# SCH_CJ4-lights-panel.net
KiCad netlist of a schematic drawn in EasyEDA
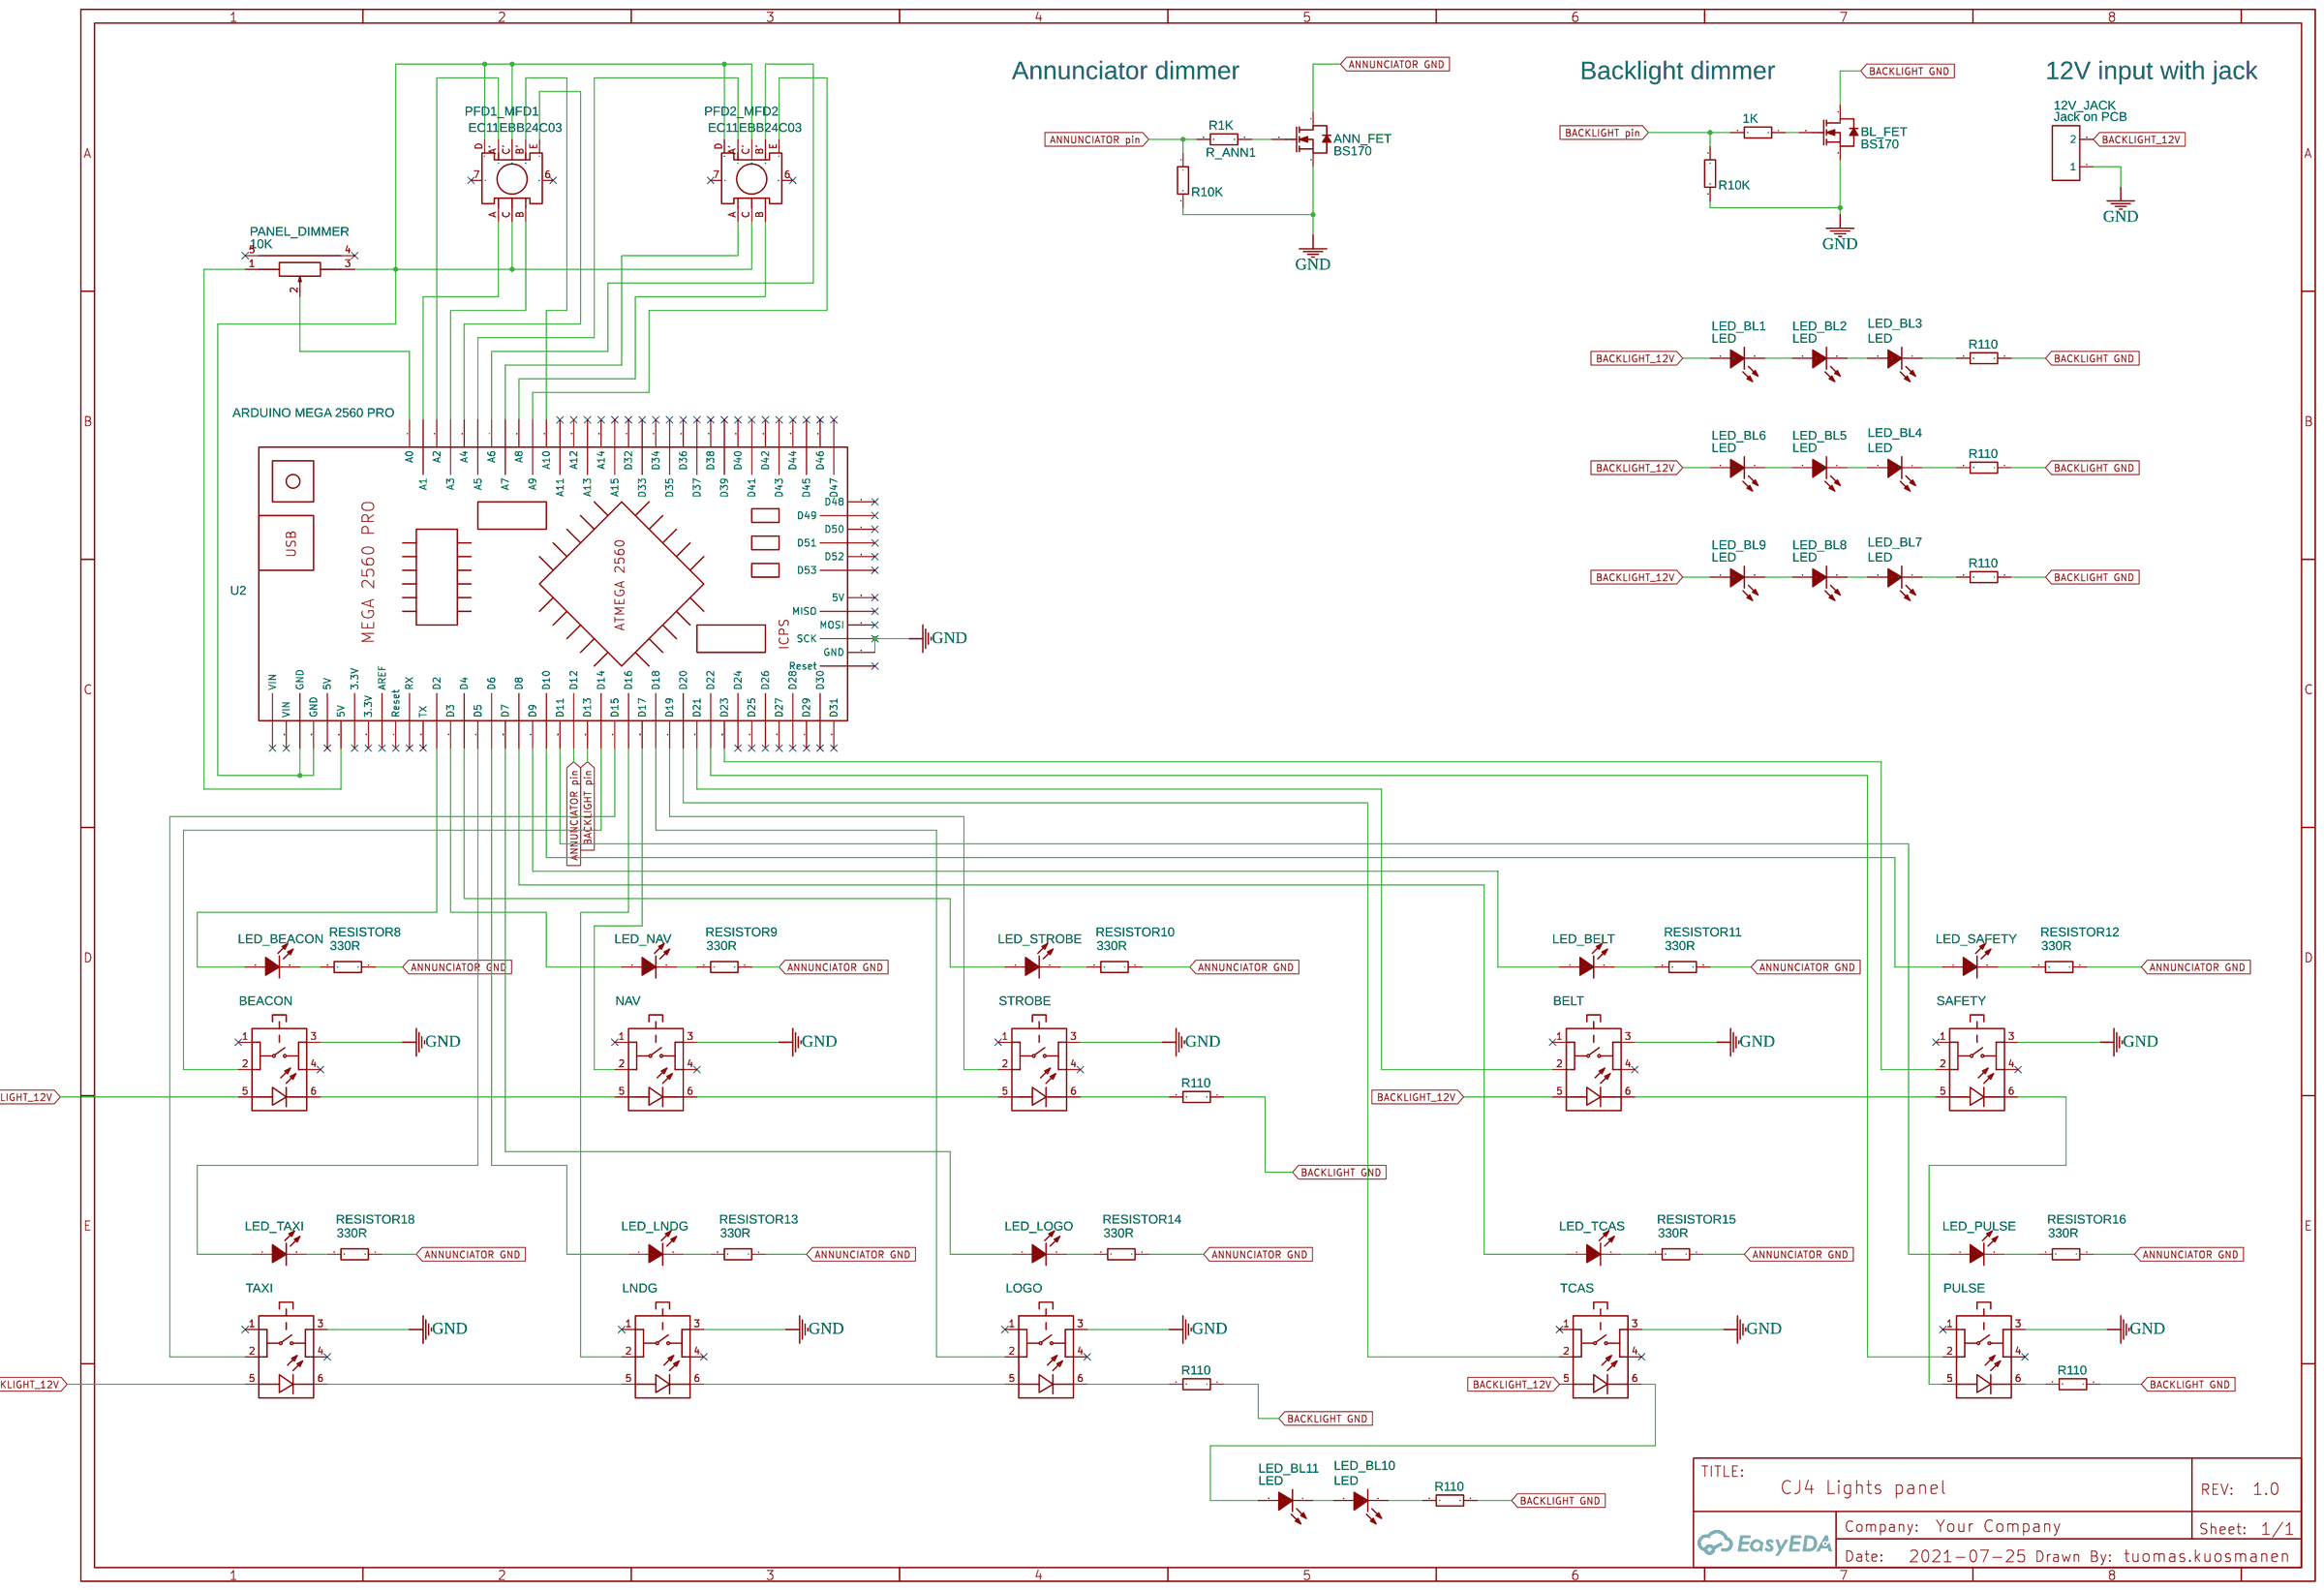
[diagram p0: schematic sheet]

(export (version "E")
  (design (tool "Eeschema 10.0.6"))
  (components
    (comp (ref "1MM_LED_THROUGH_HOLE")
      (value "LED_TAXI")
      (fields
        (field (name "BOM_Manufacturer Part") "LEDOrange orange 3AO4UD")
        (field (name "BOM_Supplier Part") "C62095")
      )
      (libsource (lib "") (part "LEDOrange orange 3AO4UD_3"))
    )
    (comp (ref "2MM_LED_THROUGH_HOLE")
      (value "LED_LNDG")
      (fields
        (field (name "BOM_Manufacturer Part") "LEDOrange orange 3AO4UD")
        (field (name "BOM_Supplier Part") "C62095")
      )
      (libsource (lib "") (part "LEDOrange orange 3AO4UD_1"))
    )
    (comp (ref "3MM_LED_THROUGH_HOLE")
      (value "LED_NAV")
      (fields
        (field (name "BOM_Manufacturer Part") "LEDOrange orange 3AO4UD")
        (field (name "BOM_Supplier Part") "C62095")
      )
      (libsource (lib "") (part "LEDOrange orange 3AO4UD_5"))
    )
    (comp (ref "4MM_LED_THROUGH_HOLE")
      (value "LED_LOGO")
      (fields
        (field (name "BOM_Manufacturer Part") "LEDOrange orange 3AO4UD")
        (field (name "BOM_Supplier Part") "C62095")
      )
      (libsource (lib "") (part "LEDOrange orange 3AO4UD_6"))
    )
    (comp (ref "5MM_LED_THROUGH_HOLE")
      (value "LED_BEACON")
      (fields
        (field (name "BOM_Manufacturer Part") "LEDOrange orange 3AO4UD")
        (field (name "BOM_Supplier Part") "C62095")
      )
      (libsource (lib "") (part "LEDOrange orange 3AO4UD_9"))
    )
    (comp (ref "6MM_LED_THROUGH_HOLE")
      (value "LED_STROBE")
      (fields
        (field (name "BOM_Manufacturer Part") "LEDOrange orange 3AO4UD")
        (field (name "BOM_Supplier Part") "C62095")
      )
      (libsource (lib "") (part "LEDOrange orange 3AO4UD_2"))
    )
    (comp (ref "7MM_LED_THROUGH_HOLE")
      (value "LED_SAFETY")
      (fields
        (field (name "BOM_Manufacturer Part") "LEDOrange orange 3AO4UD")
        (field (name "BOM_Supplier Part") "C62095")
      )
      (libsource (lib "") (part "LEDOrange orange 3AO4UD_7"))
    )
    (comp (ref "8MM_LED_THROUGH_HOLE")
      (value "LED_PULSE")
      (fields
        (field (name "BOM_Manufacturer Part") "LEDOrange orange 3AO4UD")
        (field (name "BOM_Supplier Part") "C62095")
      )
      (libsource (lib "") (part "LEDOrange orange 3AO4UD"))
    )
    (comp (ref "9MM_LED_THROUGH_HOLE")
      (value "LED_BELT")
      (fields
        (field (name "BOM_Manufacturer Part") "LEDOrange orange 3AO4UD")
        (field (name "BOM_Supplier Part") "C62095")
      )
      (libsource (lib "") (part "LEDOrange orange 3AO4UD_8"))
    )
    (comp (ref "10MM_LED_THROUGH_HOLE")
      (value "LED_TCAS")
      (fields
        (field (name "BOM_Manufacturer Part") "LEDOrange orange 3AO4UD")
        (field (name "BOM_Supplier Part") "C62095")
      )
      (libsource (lib "") (part "LEDOrange orange 3AO4UD_4"))
    )
    (comp (ref "12V_JACK") (value "Jack on PCB") (libsource (lib "") (part "J-Header-Male-2.54_1x2")))
    (comp (ref "ANN_FET")
      (value "BS170")
      (fields (field (name "BOM_Supplier Part") "C111691"))
      (libsource (lib "") (part "BS170"))
    )
    (comp (ref "BL_FET")
      (value "BS170")
      (fields (field (name "BOM_Supplier Part") "C111691"))
      (libsource (lib "") (part "BS170_1"))
    )
    (comp (ref "HEADING_HOLD1")
      (value "BEACON")
      (fields (field (name "BOM_Manufacturer Part") "1052612"))
      (libsource (lib "") (part "MULTIMEC 3FTH980 - Key Switch, 50 mA, 24 VDC, MEC"))
    )
    (comp (ref "HEADING_HOLD2")
      (value "TAXI")
      (fields (field (name "BOM_Manufacturer Part") "1052612"))
      (libsource (lib "") (part "MULTIMEC 3FTH980 - Key Switch, 50 mA, 24 VDC, MEC"))
    )
    (comp (ref "HEADING_HOLD3")
      (value "LNDG")
      (fields (field (name "BOM_Manufacturer Part") "1052612"))
      (libsource (lib "") (part "MULTIMEC 3FTH980 - Key Switch, 50 mA, 24 VDC, MEC"))
    )
    (comp (ref "HEADING_HOLD4")
      (value "NAV")
      (fields (field (name "BOM_Manufacturer Part") "1052612"))
      (libsource (lib "") (part "MULTIMEC 3FTH980 - Key Switch, 50 mA, 24 VDC, MEC"))
    )
    (comp (ref "HEADING_HOLD5")
      (value "LOGO")
      (fields (field (name "BOM_Manufacturer Part") "1052612"))
      (libsource (lib "") (part "MULTIMEC 3FTH980 - Key Switch, 50 mA, 24 VDC, MEC"))
    )
    (comp (ref "HEADING_HOLD6")
      (value "STROBE")
      (fields (field (name "BOM_Manufacturer Part") "1052612"))
      (libsource (lib "") (part "MULTIMEC 3FTH980 - Key Switch, 50 mA, 24 VDC, MEC"))
    )
    (comp (ref "HEADING_HOLD7")
      (value "SAFETY")
      (fields (field (name "BOM_Manufacturer Part") "1052612"))
      (libsource (lib "") (part "MULTIMEC 3FTH980 - Key Switch, 50 mA, 24 VDC, MEC"))
    )
    (comp (ref "HEADING_HOLD8")
      (value "PULSE")
      (fields (field (name "BOM_Manufacturer Part") "1052612"))
      (libsource (lib "") (part "MULTIMEC 3FTH980 - Key Switch, 50 mA, 24 VDC, MEC"))
    )
    (comp (ref "HEADING_HOLD9")
      (value "BELT")
      (fields (field (name "BOM_Manufacturer Part") "1052612"))
      (libsource (lib "") (part "MULTIMEC 3FTH980 - Key Switch, 50 mA, 24 VDC, MEC"))
    )
    (comp (ref "HEADING_HOLD10")
      (value "TCAS")
      (fields (field (name "BOM_Manufacturer Part") "1052612"))
      (libsource (lib "") (part "MULTIMEC 3FTH980 - Key Switch, 50 mA, 24 VDC, MEC"))
    )
    (comp (ref "LED_BL1")
      (value "LED")
      (fields
        (field (name "BOM_Manufacturer Part") "HQ17-2102UYOC")
        (field (name "BOM_Supplier Part") "C154481")
      )
      (libsource (lib "") (part "HQ17-2102UYOC"))
    )
    (comp (ref "LED_BL2")
      (value "LED")
      (fields
        (field (name "BOM_Manufacturer Part") "HQ17-2102UYOC")
        (field (name "BOM_Supplier Part") "C154481")
      )
      (libsource (lib "") (part "HQ17-2102UYOC"))
    )
    (comp (ref "LED_BL3")
      (value "LED")
      (fields
        (field (name "BOM_Manufacturer Part") "HQ17-2102UYOC")
        (field (name "BOM_Supplier Part") "C154481")
      )
      (libsource (lib "") (part "HQ17-2102UYOC"))
    )
    (comp (ref "LED_BL4")
      (value "LED")
      (fields
        (field (name "BOM_Manufacturer Part") "HQ17-2102UYOC")
        (field (name "BOM_Supplier Part") "C154481")
      )
      (libsource (lib "") (part "HQ17-2102UYOC"))
    )
    (comp (ref "LED_BL5")
      (value "LED")
      (fields
        (field (name "BOM_Manufacturer Part") "HQ17-2102UYOC")
        (field (name "BOM_Supplier Part") "C154481")
      )
      (libsource (lib "") (part "HQ17-2102UYOC"))
    )
    (comp (ref "LED_BL6")
      (value "LED")
      (fields
        (field (name "BOM_Manufacturer Part") "HQ17-2102UYOC")
        (field (name "BOM_Supplier Part") "C154481")
      )
      (libsource (lib "") (part "HQ17-2102UYOC"))
    )
    (comp (ref "LED_BL7")
      (value "LED")
      (fields
        (field (name "BOM_Manufacturer Part") "HQ17-2102UYOC")
        (field (name "BOM_Supplier Part") "C154481")
      )
      (libsource (lib "") (part "HQ17-2102UYOC"))
    )
    (comp (ref "LED_BL8")
      (value "LED")
      (fields
        (field (name "BOM_Manufacturer Part") "HQ17-2102UYOC")
        (field (name "BOM_Supplier Part") "C154481")
      )
      (libsource (lib "") (part "HQ17-2102UYOC"))
    )
    (comp (ref "LED_BL9")
      (value "LED")
      (fields
        (field (name "BOM_Manufacturer Part") "HQ17-2102UYOC")
        (field (name "BOM_Supplier Part") "C154481")
      )
      (libsource (lib "") (part "HQ17-2102UYOC"))
    )
    (comp (ref "LED_BL10")
      (value "LED")
      (fields
        (field (name "BOM_Manufacturer Part") "HQ17-2102UYOC")
        (field (name "BOM_Supplier Part") "C154481")
      )
      (libsource (lib "") (part "HQ17-2102UYOC"))
    )
    (comp (ref "LED_BL11")
      (value "LED")
      (fields
        (field (name "BOM_Manufacturer Part") "HQ17-2102UYOC")
        (field (name "BOM_Supplier Part") "C154481")
      )
      (libsource (lib "") (part "HQ17-2102UYOC"))
    )
    (comp (ref "PANEL_DIMMER")
      (value "10K")
      (fields
        (field (name "BOM_Manufacturer Part") "RK09K1130A70")
        (field (name "BOM_Supplier Part") "C351173")
      )
      (libsource (lib "") (part "RK09K1130A70"))
    )
    (comp (ref "PFD1_MFD1")
      (value "EC11EBB24C03")
      (fields (field (name "BOM_Supplier Part") "C470790"))
      (libsource (lib "") (part "EC11EBB24C03_1"))
    )
    (comp (ref "PFD2_MFD2")
      (value "EC11EBB24C03")
      (fields (field (name "BOM_Supplier Part") "C470790"))
      (libsource (lib "") (part "EC11EBB24C03"))
    )
    (comp (ref "PROTECT_BL1")
      (value "1K")
      (fields
        (field (name "BOM_Manufacturer Part") "1206W4J0331T5E")
        (field (name "BOM_Supplier Part") "C25374")
      )
      (libsource (lib "") (part "1206W4J0331T5E_3"))
    )
    (comp (ref "RESISTOR8")
      (value "330R")
      (fields
        (field (name "BOM_Manufacturer Part") "1206W4J0331T5E")
        (field (name "BOM_Supplier Part") "C25374")
      )
      (libsource (lib "") (part "1206W4J0331T5E"))
    )
    (comp (ref "RESISTOR9")
      (value "330R")
      (fields
        (field (name "BOM_Manufacturer Part") "1206W4J0331T5E")
        (field (name "BOM_Supplier Part") "C25374")
      )
      (libsource (lib "") (part "1206W4J0331T5E"))
    )
    (comp (ref "RESISTOR10")
      (value "330R")
      (fields
        (field (name "BOM_Manufacturer Part") "1206W4J0331T5E")
        (field (name "BOM_Supplier Part") "C25374")
      )
      (libsource (lib "") (part "1206W4J0331T5E"))
    )
    (comp (ref "RESISTOR11")
      (value "330R")
      (fields
        (field (name "BOM_Manufacturer Part") "1206W4J0331T5E")
        (field (name "BOM_Supplier Part") "C25374")
      )
      (libsource (lib "") (part "1206W4J0331T5E"))
    )
    (comp (ref "RESISTOR12")
      (value "330R")
      (fields
        (field (name "BOM_Manufacturer Part") "1206W4J0331T5E")
        (field (name "BOM_Supplier Part") "C25374")
      )
      (libsource (lib "") (part "1206W4J0331T5E"))
    )
    (comp (ref "RESISTOR13")
      (value "330R")
      (fields
        (field (name "BOM_Manufacturer Part") "1206W4J0331T5E")
        (field (name "BOM_Supplier Part") "C25374")
      )
      (libsource (lib "") (part "1206W4J0331T5E"))
    )
    (comp (ref "RESISTOR14")
      (value "330R")
      (fields
        (field (name "BOM_Manufacturer Part") "1206W4J0331T5E")
        (field (name "BOM_Supplier Part") "C25374")
      )
      (libsource (lib "") (part "1206W4J0331T5E"))
    )
    (comp (ref "RESISTOR15")
      (value "330R")
      (fields
        (field (name "BOM_Manufacturer Part") "1206W4J0331T5E")
        (field (name "BOM_Supplier Part") "C25374")
      )
      (libsource (lib "") (part "1206W4J0331T5E"))
    )
    (comp (ref "RESISTOR16")
      (value "330R")
      (fields
        (field (name "BOM_Manufacturer Part") "1206W4J0331T5E")
        (field (name "BOM_Supplier Part") "C25374")
      )
      (libsource (lib "") (part "1206W4J0331T5E"))
    )
    (comp (ref "RESISTOR18")
      (value "330R")
      (fields
        (field (name "BOM_Manufacturer Part") "1206W4J0331T5E")
        (field (name "BOM_Supplier Part") "C25374")
      )
      (libsource (lib "") (part "1206W4J0331T5E"))
    )
    (comp (ref "R_ANN1")
      (value "R1K")
      (fields
        (field (name "BOM_Manufacturer Part") "1206W4J0331T5E")
        (field (name "BOM_Supplier Part") "C25374")
      )
      (libsource (lib "") (part "1206W4J0331T5E_4"))
    )
    (comp (ref "R_ANN2")
      (value "R10K")
      (fields
        (field (name "BOM_Manufacturer Part") "1206W4J0331T5E")
        (field (name "BOM_Supplier Part") "C25374")
      )
      (libsource (lib "") (part "1206W4J0331T5E_2"))
    )
    (comp (ref "R_ANN5")
      (value "R10K")
      (fields
        (field (name "BOM_Manufacturer Part") "1206W4J0331T5E")
        (field (name "BOM_Supplier Part") "C25374")
      )
      (libsource (lib "") (part "1206W4J0331T5E_2"))
    )
    (comp (ref "R_BL1")
      (value "R110")
      (fields
        (field (name "BOM_Manufacturer Part") "1206W4J0331T5E")
        (field (name "BOM_Supplier Part") "C25374")
      )
      (libsource (lib "") (part "1206W4J0331T5E_1"))
    )
    (comp (ref "R_BL2")
      (value "R110")
      (fields
        (field (name "BOM_Manufacturer Part") "1206W4J0331T5E")
        (field (name "BOM_Supplier Part") "C25374")
      )
      (libsource (lib "") (part "1206W4J0331T5E_1"))
    )
    (comp (ref "R_BL3")
      (value "R110")
      (fields
        (field (name "BOM_Manufacturer Part") "1206W4J0331T5E")
        (field (name "BOM_Supplier Part") "C25374")
      )
      (libsource (lib "") (part "1206W4J0331T5E_1"))
    )
    (comp (ref "R_BL4")
      (value "R110")
      (fields
        (field (name "BOM_Manufacturer Part") "1206W4J0331T5E")
        (field (name "BOM_Supplier Part") "C25374")
      )
      (libsource (lib "") (part "1206W4J0331T5E_1"))
    )
    (comp (ref "R_BL5")
      (value "R110")
      (fields
        (field (name "BOM_Manufacturer Part") "1206W4J0331T5E")
        (field (name "BOM_Supplier Part") "C25374")
      )
      (libsource (lib "") (part "1206W4J0331T5E_1"))
    )
    (comp (ref "R_BL6")
      (value "R110")
      (fields
        (field (name "BOM_Manufacturer Part") "1206W4J0331T5E")
        (field (name "BOM_Supplier Part") "C25374")
      )
      (libsource (lib "") (part "1206W4J0331T5E_1"))
    )
    (comp (ref "R_BL7")
      (value "R110")
      (fields
        (field (name "BOM_Manufacturer Part") "1206W4J0331T5E")
        (field (name "BOM_Supplier Part") "C25374")
      )
      (libsource (lib "") (part "1206W4J0331T5E_1"))
    )
    (comp (ref "U2")
      (value "ARDUINO MEGA 2560 PRO")
      (fields (field (name "BOM_Manufacturer Part") "Arduino Mega 2560 Pro Mini"))
      (libsource (lib "") (part "ARDUINO MEGA 2560 PRO"))
    )
  )
  (nets
    (net (code "1") (name "ANNUNCIATOR GND") (class "Default")
      (node (ref "ANN_FET") (pin "1") (pinfunction "D_1") (pintype "unspecified"))
      (node (ref "RESISTOR10") (pin "1") (pinfunction "1_1") (pintype "input"))
      (node (ref "RESISTOR11") (pin "1") (pinfunction "1_1") (pintype "input"))
      (node (ref "RESISTOR12") (pin "1") (pinfunction "1_1") (pintype "input"))
      (node (ref "RESISTOR13") (pin "1") (pinfunction "1_1") (pintype "input"))
      (node (ref "RESISTOR14") (pin "1") (pinfunction "1_1") (pintype "input"))
      (node (ref "RESISTOR15") (pin "1") (pinfunction "1_1") (pintype "input"))
      (node (ref "RESISTOR16") (pin "1") (pinfunction "1_1") (pintype "input"))
      (node (ref "RESISTOR18") (pin "1") (pinfunction "1_1") (pintype "input"))
      (node (ref "RESISTOR8") (pin "1") (pinfunction "1_1") (pintype "input"))
      (node (ref "RESISTOR9") (pin "1") (pinfunction "1_1") (pintype "input"))
    )
    (net (code "2") (name "ANNUNCIATOR pin") (class "Default")
      (node (ref "R_ANN1") (pin "2") (pinfunction "2_2") (pintype "input"))
      (node (ref "R_ANN2") (pin "1") (pinfunction "1_1") (pintype "input"))
      (node (ref "U2") (pin "64") (pinfunction "D12_64") (pintype "unspecified"))
    )
    (net (code "3") (name "BACKLIGHT GND") (class "Default")
      (node (ref "BL_FET") (pin "1") (pinfunction "D_1") (pintype "unspecified"))
      (node (ref "R_BL1") (pin "1") (pinfunction "1_1") (pintype "input"))
      (node (ref "R_BL2") (pin "1") (pinfunction "1_1") (pintype "input"))
      (node (ref "R_BL3") (pin "1") (pinfunction "1_1") (pintype "input"))
      (node (ref "R_BL4") (pin "1") (pinfunction "1_1") (pintype "input"))
      (node (ref "R_BL5") (pin "1") (pinfunction "1_1") (pintype "input"))
      (node (ref "R_BL6") (pin "1") (pinfunction "1_1") (pintype "input"))
      (node (ref "R_BL7") (pin "1") (pinfunction "1_1") (pintype "input"))
    )
    (net (code "4") (name "BACKLIGHT pin") (class "Default")
      (node (ref "PROTECT_BL1") (pin "2") (pinfunction "2_2") (pintype "input"))
      (node (ref "R_ANN5") (pin "1") (pinfunction "1_1") (pintype "input"))
      (node (ref "U2") (pin "63") (pinfunction "D13_63") (pintype "unspecified"))
    )
    (net (code "5") (name "BACKLIGHT_12V") (class "Default")
      (node (ref "12V_JACK") (pin "2") (pinfunction "2_2") (pintype "unspecified"))
      (node (ref "HEADING_HOLD1") (pin "5") (pinfunction "2_5") (pintype "unspecified"))
      (node (ref "HEADING_HOLD10") (pin "5") (pinfunction "2_5") (pintype "unspecified"))
      (node (ref "HEADING_HOLD2") (pin "5") (pinfunction "2_5") (pintype "unspecified"))
      (node (ref "HEADING_HOLD9") (pin "5") (pinfunction "2_5") (pintype "unspecified"))
      (node (ref "LED_BL1") (pin "2") (pinfunction "A_2") (pintype "unspecified"))
      (node (ref "LED_BL6") (pin "2") (pinfunction "A_2") (pintype "unspecified"))
      (node (ref "LED_BL9") (pin "2") (pinfunction "A_2") (pintype "unspecified"))
    )
    (net (code "6") (name "GND") (class "Default")
      (node (ref "12V_JACK") (pin "1") (pinfunction "1_1") (pintype "unspecified"))
      (node (ref "ANN_FET") (pin "3") (pinfunction "S_3") (pintype "unspecified"))
      (node (ref "BL_FET") (pin "3") (pinfunction "S_3") (pintype "unspecified"))
      (node (ref "HEADING_HOLD1") (pin "3") (pinfunction "3_3") (pintype "unspecified"))
      (node (ref "HEADING_HOLD10") (pin "3") (pinfunction "3_3") (pintype "unspecified"))
      (node (ref "HEADING_HOLD2") (pin "3") (pinfunction "3_3") (pintype "unspecified"))
      (node (ref "HEADING_HOLD3") (pin "3") (pinfunction "3_3") (pintype "unspecified"))
      (node (ref "HEADING_HOLD4") (pin "3") (pinfunction "3_3") (pintype "unspecified"))
      (node (ref "HEADING_HOLD5") (pin "3") (pinfunction "3_3") (pintype "unspecified"))
      (node (ref "HEADING_HOLD6") (pin "3") (pinfunction "3_3") (pintype "unspecified"))
      (node (ref "HEADING_HOLD7") (pin "3") (pinfunction "3_3") (pintype "unspecified"))
      (node (ref "HEADING_HOLD8") (pin "3") (pinfunction "3_3") (pintype "unspecified"))
      (node (ref "HEADING_HOLD9") (pin "3") (pinfunction "3_3") (pintype "unspecified"))
      (node (ref "R_ANN2") (pin "2") (pinfunction "2_2") (pintype "input"))
      (node (ref "R_ANN5") (pin "2") (pinfunction "2_2") (pintype "input"))
      (node (ref "U2") (pin "42") (pinfunction "SCK_42") (pintype "unspecified"))
      (node (ref "U2") (pin "43") (pinfunction "GND_43") (pintype "unspecified"))
    )
    (net (code "7") (name "Net-(1MM_LED_THROUGH_HOLE-A)") (class "Default")
      (node (ref "1MM_LED_THROUGH_HOLE") (pin "1") (pinfunction "A_1") (pintype "unspecified"))
      (node (ref "U2") (pin "71") (pinfunction "D5_71") (pintype "unspecified"))
    )
    (net (code "8") (name "Net-(1MM_LED_THROUGH_HOLE-K)") (class "Default")
      (node (ref "1MM_LED_THROUGH_HOLE") (pin "2") (pinfunction "K_2") (pintype "unspecified"))
      (node (ref "RESISTOR18") (pin "2") (pinfunction "2_2") (pintype "input"))
    )
    (net (code "9") (name "Net-(2MM_LED_THROUGH_HOLE-A)") (class "Default")
      (node (ref "2MM_LED_THROUGH_HOLE") (pin "1") (pinfunction "A_1") (pintype "unspecified"))
      (node (ref "U2") (pin "70") (pinfunction "D6_70") (pintype "unspecified"))
    )
    (net (code "10") (name "Net-(2MM_LED_THROUGH_HOLE-K)") (class "Default")
      (node (ref "2MM_LED_THROUGH_HOLE") (pin "2") (pinfunction "K_2") (pintype "unspecified"))
      (node (ref "RESISTOR13") (pin "2") (pinfunction "2_2") (pintype "input"))
    )
    (net (code "11") (name "Net-(3MM_LED_THROUGH_HOLE-A)") (class "Default")
      (node (ref "3MM_LED_THROUGH_HOLE") (pin "1") (pinfunction "A_1") (pintype "unspecified"))
      (node (ref "U2") (pin "73") (pinfunction "D3_73") (pintype "unspecified"))
    )
    (net (code "12") (name "Net-(3MM_LED_THROUGH_HOLE-K)") (class "Default")
      (node (ref "3MM_LED_THROUGH_HOLE") (pin "2") (pinfunction "K_2") (pintype "unspecified"))
      (node (ref "RESISTOR9") (pin "2") (pinfunction "2_2") (pintype "input"))
    )
    (net (code "13") (name "Net-(4MM_LED_THROUGH_HOLE-A)") (class "Default")
      (node (ref "4MM_LED_THROUGH_HOLE") (pin "1") (pinfunction "A_1") (pintype "unspecified"))
      (node (ref "U2") (pin "69") (pinfunction "D7_69") (pintype "unspecified"))
    )
    (net (code "14") (name "Net-(4MM_LED_THROUGH_HOLE-K)") (class "Default")
      (node (ref "4MM_LED_THROUGH_HOLE") (pin "2") (pinfunction "K_2") (pintype "unspecified"))
      (node (ref "RESISTOR14") (pin "2") (pinfunction "2_2") (pintype "input"))
    )
    (net (code "15") (name "Net-(5MM_LED_THROUGH_HOLE-A)") (class "Default")
      (node (ref "5MM_LED_THROUGH_HOLE") (pin "1") (pinfunction "A_1") (pintype "unspecified"))
      (node (ref "U2") (pin "74") (pinfunction "D2_74") (pintype "unspecified"))
    )
    (net (code "16") (name "Net-(5MM_LED_THROUGH_HOLE-K)") (class "Default")
      (node (ref "5MM_LED_THROUGH_HOLE") (pin "2") (pinfunction "K_2") (pintype "unspecified"))
      (node (ref "RESISTOR8") (pin "2") (pinfunction "2_2") (pintype "input"))
    )
    (net (code "17") (name "Net-(6MM_LED_THROUGH_HOLE-A)") (class "Default")
      (node (ref "6MM_LED_THROUGH_HOLE") (pin "1") (pinfunction "A_1") (pintype "unspecified"))
      (node (ref "U2") (pin "72") (pinfunction "D4_72") (pintype "unspecified"))
    )
    (net (code "18") (name "Net-(6MM_LED_THROUGH_HOLE-K)") (class "Default")
      (node (ref "6MM_LED_THROUGH_HOLE") (pin "2") (pinfunction "K_2") (pintype "unspecified"))
      (node (ref "RESISTOR10") (pin "2") (pinfunction "2_2") (pintype "input"))
    )
    (net (code "19") (name "Net-(7MM_LED_THROUGH_HOLE-A)") (class "Default")
      (node (ref "7MM_LED_THROUGH_HOLE") (pin "1") (pinfunction "A_1") (pintype "unspecified"))
      (node (ref "U2") (pin "66") (pinfunction "D10_66") (pintype "unspecified"))
    )
    (net (code "20") (name "Net-(7MM_LED_THROUGH_HOLE-K)") (class "Default")
      (node (ref "7MM_LED_THROUGH_HOLE") (pin "2") (pinfunction "K_2") (pintype "unspecified"))
      (node (ref "RESISTOR12") (pin "2") (pinfunction "2_2") (pintype "input"))
    )
    (net (code "21") (name "Net-(8MM_LED_THROUGH_HOLE-A)") (class "Default")
      (node (ref "8MM_LED_THROUGH_HOLE") (pin "1") (pinfunction "A_1") (pintype "unspecified"))
      (node (ref "U2") (pin "65") (pinfunction "D11_65") (pintype "unspecified"))
    )
    (net (code "22") (name "Net-(8MM_LED_THROUGH_HOLE-K)") (class "Default")
      (node (ref "8MM_LED_THROUGH_HOLE") (pin "2") (pinfunction "K_2") (pintype "unspecified"))
      (node (ref "RESISTOR16") (pin "2") (pinfunction "2_2") (pintype "input"))
    )
    (net (code "23") (name "Net-(9MM_LED_THROUGH_HOLE-A)") (class "Default")
      (node (ref "9MM_LED_THROUGH_HOLE") (pin "1") (pinfunction "A_1") (pintype "unspecified"))
      (node (ref "U2") (pin "67") (pinfunction "D9_67") (pintype "unspecified"))
    )
    (net (code "24") (name "Net-(9MM_LED_THROUGH_HOLE-K)") (class "Default")
      (node (ref "9MM_LED_THROUGH_HOLE") (pin "2") (pinfunction "K_2") (pintype "unspecified"))
      (node (ref "RESISTOR11") (pin "2") (pinfunction "2_2") (pintype "input"))
    )
    (net (code "25") (name "Net-(10MM_LED_THROUGH_HOLE-A)") (class "Default")
      (node (ref "10MM_LED_THROUGH_HOLE") (pin "1") (pinfunction "A_1") (pintype "unspecified"))
      (node (ref "U2") (pin "68") (pinfunction "D8_68") (pintype "unspecified"))
    )
    (net (code "26") (name "Net-(10MM_LED_THROUGH_HOLE-K)") (class "Default")
      (node (ref "10MM_LED_THROUGH_HOLE") (pin "2") (pinfunction "K_2") (pintype "unspecified"))
      (node (ref "RESISTOR15") (pin "2") (pinfunction "2_2") (pintype "input"))
    )
    (net (code "27") (name "Net-(ANN_FET-G)") (class "Default")
      (node (ref "ANN_FET") (pin "2") (pinfunction "G_2") (pintype "unspecified"))
      (node (ref "R_ANN1") (pin "1") (pinfunction "1_1") (pintype "input"))
    )
    (net (code "28") (name "Net-(BL_FET-G)") (class "Default")
      (node (ref "BL_FET") (pin "2") (pinfunction "G_2") (pintype "unspecified"))
      (node (ref "PROTECT_BL1") (pin "1") (pinfunction "1_1") (pintype "input"))
    )
    (net (code "29") (name "Net-(HEADING_HOLD1-4-Pad6)") (class "Default")
      (node (ref "HEADING_HOLD1") (pin "6") (pinfunction "4_6") (pintype "unspecified"))
      (node (ref "HEADING_HOLD4") (pin "5") (pinfunction "2_5") (pintype "unspecified"))
    )
    (net (code "30") (name "Net-(HEADING_HOLD2-4-Pad6)") (class "Default")
      (node (ref "HEADING_HOLD2") (pin "6") (pinfunction "4_6") (pintype "unspecified"))
      (node (ref "HEADING_HOLD3") (pin "5") (pinfunction "2_5") (pintype "unspecified"))
    )
    (net (code "31") (name "Net-(HEADING_HOLD3-4-Pad6)") (class "Default")
      (node (ref "HEADING_HOLD3") (pin "6") (pinfunction "4_6") (pintype "unspecified"))
      (node (ref "HEADING_HOLD5") (pin "5") (pinfunction "2_5") (pintype "unspecified"))
    )
    (net (code "32") (name "Net-(HEADING_HOLD4-4-Pad6)") (class "Default")
      (node (ref "HEADING_HOLD4") (pin "6") (pinfunction "4_6") (pintype "unspecified"))
      (node (ref "HEADING_HOLD6") (pin "5") (pinfunction "2_5") (pintype "unspecified"))
    )
    (net (code "33") (name "Net-(HEADING_HOLD5-4-Pad6)") (class "Default")
      (node (ref "HEADING_HOLD5") (pin "6") (pinfunction "4_6") (pintype "unspecified"))
      (node (ref "R_BL6") (pin "2") (pinfunction "2_2") (pintype "input"))
    )
    (net (code "34") (name "Net-(HEADING_HOLD6-4-Pad6)") (class "Default")
      (node (ref "HEADING_HOLD6") (pin "6") (pinfunction "4_6") (pintype "unspecified"))
      (node (ref "R_BL5") (pin "2") (pinfunction "2_2") (pintype "input"))
    )
    (net (code "35") (name "Net-(HEADING_HOLD7-2-Pad5)") (class "Default")
      (node (ref "HEADING_HOLD7") (pin "5") (pinfunction "2_5") (pintype "unspecified"))
      (node (ref "HEADING_HOLD9") (pin "6") (pinfunction "4_6") (pintype "unspecified"))
    )
    (net (code "36") (name "Net-(HEADING_HOLD7-4-Pad6)") (class "Default")
      (node (ref "HEADING_HOLD7") (pin "6") (pinfunction "4_6") (pintype "unspecified"))
      (node (ref "HEADING_HOLD8") (pin "5") (pinfunction "2_5") (pintype "unspecified"))
    )
    (net (code "37") (name "Net-(HEADING_HOLD8-4-Pad6)") (class "Default")
      (node (ref "HEADING_HOLD8") (pin "6") (pinfunction "4_6") (pintype "unspecified"))
      (node (ref "R_BL7") (pin "2") (pinfunction "2_2") (pintype "input"))
    )
    (net (code "38") (name "Net-(LED_BL1-K)") (class "Default")
      (node (ref "LED_BL1") (pin "1") (pinfunction "K_1") (pintype "unspecified"))
      (node (ref "LED_BL2") (pin "2") (pinfunction "A_2") (pintype "unspecified"))
    )
    (net (code "39") (name "Net-(LED_BL2-K)") (class "Default")
      (node (ref "LED_BL2") (pin "1") (pinfunction "K_1") (pintype "unspecified"))
      (node (ref "LED_BL3") (pin "2") (pinfunction "A_2") (pintype "unspecified"))
    )
    (net (code "40") (name "Net-(LED_BL3-K)") (class "Default")
      (node (ref "LED_BL3") (pin "1") (pinfunction "K_1") (pintype "unspecified"))
      (node (ref "R_BL1") (pin "2") (pinfunction "2_2") (pintype "input"))
    )
    (net (code "41") (name "Net-(LED_BL4-A)") (class "Default")
      (node (ref "LED_BL4") (pin "2") (pinfunction "A_2") (pintype "unspecified"))
      (node (ref "LED_BL5") (pin "1") (pinfunction "K_1") (pintype "unspecified"))
    )
    (net (code "42") (name "Net-(LED_BL4-K)") (class "Default")
      (node (ref "LED_BL4") (pin "1") (pinfunction "K_1") (pintype "unspecified"))
      (node (ref "R_BL2") (pin "2") (pinfunction "2_2") (pintype "input"))
    )
    (net (code "43") (name "Net-(LED_BL5-A)") (class "Default")
      (node (ref "LED_BL5") (pin "2") (pinfunction "A_2") (pintype "unspecified"))
      (node (ref "LED_BL6") (pin "1") (pinfunction "K_1") (pintype "unspecified"))
    )
    (net (code "44") (name "Net-(LED_BL7-A)") (class "Default")
      (node (ref "LED_BL7") (pin "2") (pinfunction "A_2") (pintype "unspecified"))
      (node (ref "LED_BL8") (pin "1") (pinfunction "K_1") (pintype "unspecified"))
    )
    (net (code "45") (name "Net-(LED_BL7-K)") (class "Default")
      (node (ref "LED_BL7") (pin "1") (pinfunction "K_1") (pintype "unspecified"))
      (node (ref "R_BL3") (pin "2") (pinfunction "2_2") (pintype "input"))
    )
    (net (code "46") (name "Net-(LED_BL8-A)") (class "Default")
      (node (ref "LED_BL8") (pin "2") (pinfunction "A_2") (pintype "unspecified"))
      (node (ref "LED_BL9") (pin "1") (pinfunction "K_1") (pintype "unspecified"))
    )
    (net (code "47") (name "Net-(LED_BL10-A)") (class "Default")
      (node (ref "LED_BL10") (pin "2") (pinfunction "A_2") (pintype "unspecified"))
      (node (ref "LED_BL11") (pin "1") (pinfunction "K_1") (pintype "unspecified"))
    )
    (net (code "48") (name "Net-(LED_BL10-K)") (class "Default")
      (node (ref "LED_BL10") (pin "1") (pinfunction "K_1") (pintype "unspecified"))
      (node (ref "R_BL4") (pin "2") (pinfunction "2_2") (pintype "input"))
    )
    (net (code "49") (name "Net-(LED_BL11-A)") (class "Default")
      (node (ref "HEADING_HOLD10") (pin "6") (pinfunction "4_6") (pintype "unspecified"))
      (node (ref "LED_BL11") (pin "2") (pinfunction "A_2") (pintype "unspecified"))
    )
    (net (code "50") (name "Net-(PANEL_DIMMER-Pad1)") (class "Default")
      (node (ref "PANEL_DIMMER") (pin "1") (pinfunction "1_1") (pintype "unspecified"))
      (node (ref "U2") (pin "81") (pinfunction "5V_81") (pintype "unspecified"))
    )
    (net (code "51") (name "Net-(PANEL_DIMMER-Pad3)") (class "Default")
      (node (ref "PANEL_DIMMER") (pin "3") (pinfunction "3_3") (pintype "unspecified"))
      (node (ref "PFD1_MFD1") (pin "C") (pinfunction "C_C") (pintype "unspecified"))
      (node (ref "PFD1_MFD1") (pin "C'") (pinfunction "C'_C'") (pintype "unspecified"))
      (node (ref "PFD1_MFD1") (pin "D") (pinfunction "D_D") (pintype "unspecified"))
      (node (ref "PFD2_MFD2") (pin "C") (pinfunction "C_C") (pintype "unspecified"))
      (node (ref "PFD2_MFD2") (pin "C'") (pinfunction "C'_C'") (pintype "unspecified"))
      (node (ref "PFD2_MFD2") (pin "D") (pinfunction "D_D") (pintype "unspecified"))
      (node (ref "U2") (pin "83") (pinfunction "GND_83") (pintype "unspecified"))
      (node (ref "U2") (pin "84") (pinfunction "GND_84") (pintype "unspecified"))
    )
    (net (code "52") (name "Net-(U2-A0)") (class "Default")
      (node (ref "PANEL_DIMMER") (pin "2") (pinfunction "2_2") (pintype "unspecified"))
      (node (ref "U2") (pin "1") (pinfunction "A0_1") (pintype "unspecified"))
    )
    (net (code "53") (name "Net-(U2-A1)") (class "Default")
      (node (ref "PFD1_MFD1") (pin "A") (pinfunction "A_A") (pintype "unspecified"))
      (node (ref "U2") (pin "2") (pinfunction "A1_2") (pintype "unspecified"))
    )
    (net (code "54") (name "Net-(U2-A2)") (class "Default")
      (node (ref "PFD1_MFD1") (pin "A'") (pinfunction "A'_A'") (pintype "unspecified"))
      (node (ref "U2") (pin "3") (pinfunction "A2_3") (pintype "unspecified"))
    )
    (net (code "55") (name "Net-(U2-A3)") (class "Default")
      (node (ref "PFD1_MFD1") (pin "B") (pinfunction "B_B") (pintype "unspecified"))
      (node (ref "U2") (pin "4") (pinfunction "A3_4") (pintype "unspecified"))
    )
    (net (code "56") (name "Net-(U2-A4)") (class "Default")
      (node (ref "PFD1_MFD1") (pin "E") (pinfunction "E_E") (pintype "unspecified"))
      (node (ref "U2") (pin "5") (pinfunction "A4_5") (pintype "unspecified"))
    )
    (net (code "57") (name "Net-(U2-A5)") (class "Default")
      (node (ref "PFD2_MFD2") (pin "A'") (pinfunction "A'_A'") (pintype "unspecified"))
      (node (ref "U2") (pin "6") (pinfunction "A5_6") (pintype "unspecified"))
    )
    (net (code "58") (name "Net-(U2-A6)") (class "Default")
      (node (ref "PFD2_MFD2") (pin "B'") (pinfunction "B'_B'") (pintype "unspecified"))
      (node (ref "U2") (pin "7") (pinfunction "A6_7") (pintype "unspecified"))
    )
    (net (code "59") (name "Net-(U2-A7)") (class "Default")
      (node (ref "PFD2_MFD2") (pin "A") (pinfunction "A_A") (pintype "unspecified"))
      (node (ref "U2") (pin "8") (pinfunction "A7_8") (pintype "unspecified"))
    )
    (net (code "60") (name "Net-(U2-A8)") (class "Default")
      (node (ref "PFD2_MFD2") (pin "B") (pinfunction "B_B") (pintype "unspecified"))
      (node (ref "U2") (pin "9") (pinfunction "A8_9") (pintype "unspecified"))
    )
    (net (code "61") (name "Net-(U2-A9)") (class "Default")
      (node (ref "PFD2_MFD2") (pin "E") (pinfunction "E_E") (pintype "unspecified"))
      (node (ref "U2") (pin "10") (pinfunction "A9_10") (pintype "unspecified"))
    )
    (net (code "62") (name "Net-(U2-A10)") (class "Default")
      (node (ref "PFD1_MFD1") (pin "B'") (pinfunction "B'_B'") (pintype "unspecified"))
      (node (ref "U2") (pin "11") (pinfunction "A10_11") (pintype "unspecified"))
    )
    (net (code "63") (name "Net-(U2-D14)") (class "Default")
      (node (ref "HEADING_HOLD1") (pin "2") (pinfunction "2_2") (pintype "unspecified"))
      (node (ref "U2") (pin "62") (pinfunction "D14_62") (pintype "unspecified"))
    )
    (net (code "64") (name "Net-(U2-D15)") (class "Default")
      (node (ref "HEADING_HOLD2") (pin "2") (pinfunction "2_2") (pintype "unspecified"))
      (node (ref "U2") (pin "61") (pinfunction "D15_61") (pintype "unspecified"))
    )
    (net (code "65") (name "Net-(U2-D16)") (class "Default")
      (node (ref "HEADING_HOLD3") (pin "2") (pinfunction "2_2") (pintype "unspecified"))
      (node (ref "U2") (pin "60") (pinfunction "D16_60") (pintype "unspecified"))
    )
    (net (code "66") (name "Net-(U2-D17)") (class "Default")
      (node (ref "HEADING_HOLD4") (pin "2") (pinfunction "2_2") (pintype "unspecified"))
      (node (ref "U2") (pin "59") (pinfunction "D17_59") (pintype "unspecified"))
    )
    (net (code "67") (name "Net-(U2-D18)") (class "Default")
      (node (ref "HEADING_HOLD5") (pin "2") (pinfunction "2_2") (pintype "unspecified"))
      (node (ref "U2") (pin "58") (pinfunction "D18_58") (pintype "unspecified"))
    )
    (net (code "68") (name "Net-(U2-D19)") (class "Default")
      (node (ref "HEADING_HOLD6") (pin "2") (pinfunction "2_2") (pintype "unspecified"))
      (node (ref "U2") (pin "57") (pinfunction "D19_57") (pintype "unspecified"))
    )
    (net (code "69") (name "Net-(U2-D20)") (class "Default")
      (node (ref "HEADING_HOLD10") (pin "2") (pinfunction "2_2") (pintype "unspecified"))
      (node (ref "U2") (pin "56") (pinfunction "D20_56") (pintype "unspecified"))
    )
    (net (code "70") (name "Net-(U2-D21)") (class "Default")
      (node (ref "HEADING_HOLD9") (pin "2") (pinfunction "2_2") (pintype "unspecified"))
      (node (ref "U2") (pin "55") (pinfunction "D21_55") (pintype "unspecified"))
    )
    (net (code "71") (name "Net-(U2-D22)") (class "Default")
      (node (ref "HEADING_HOLD8") (pin "2") (pinfunction "2_2") (pintype "unspecified"))
      (node (ref "U2") (pin "54") (pinfunction "D22_54") (pintype "unspecified"))
    )
    (net (code "72") (name "Net-(U2-D23)") (class "Default")
      (node (ref "HEADING_HOLD7") (pin "2") (pinfunction "2_2") (pintype "unspecified"))
      (node (ref "U2") (pin "53") (pinfunction "D23_53") (pintype "unspecified"))
    )
    (net (code "73") (name "unconnected-(HEADING_HOLD1-Pad1)") (class "Default")
      (node (ref "HEADING_HOLD1") (pin "1") (pinfunction "1_1") (pintype "unspecified+no_connect"))
    )
    (net (code "74") (name "unconnected-(HEADING_HOLD1-Pad4)") (class "Default")
      (node (ref "HEADING_HOLD1") (pin "4") (pinfunction "4_4") (pintype "unspecified+no_connect"))
    )
    (net (code "75") (name "unconnected-(HEADING_HOLD2-Pad1)") (class "Default")
      (node (ref "HEADING_HOLD2") (pin "1") (pinfunction "1_1") (pintype "unspecified+no_connect"))
    )
    (net (code "76") (name "unconnected-(HEADING_HOLD2-Pad4)") (class "Default")
      (node (ref "HEADING_HOLD2") (pin "4") (pinfunction "4_4") (pintype "unspecified+no_connect"))
    )
    (net (code "77") (name "unconnected-(HEADING_HOLD3-Pad1)") (class "Default")
      (node (ref "HEADING_HOLD3") (pin "1") (pinfunction "1_1") (pintype "unspecified+no_connect"))
    )
    (net (code "78") (name "unconnected-(HEADING_HOLD3-Pad4)") (class "Default")
      (node (ref "HEADING_HOLD3") (pin "4") (pinfunction "4_4") (pintype "unspecified+no_connect"))
    )
    (net (code "79") (name "unconnected-(HEADING_HOLD4-Pad1)") (class "Default")
      (node (ref "HEADING_HOLD4") (pin "1") (pinfunction "1_1") (pintype "unspecified+no_connect"))
    )
    (net (code "80") (name "unconnected-(HEADING_HOLD4-Pad4)") (class "Default")
      (node (ref "HEADING_HOLD4") (pin "4") (pinfunction "4_4") (pintype "unspecified+no_connect"))
    )
    (net (code "81") (name "unconnected-(HEADING_HOLD5-Pad1)") (class "Default")
      (node (ref "HEADING_HOLD5") (pin "1") (pinfunction "1_1") (pintype "unspecified+no_connect"))
    )
    (net (code "82") (name "unconnected-(HEADING_HOLD5-Pad4)") (class "Default")
      (node (ref "HEADING_HOLD5") (pin "4") (pinfunction "4_4") (pintype "unspecified+no_connect"))
    )
    (net (code "83") (name "unconnected-(HEADING_HOLD6-Pad1)") (class "Default")
      (node (ref "HEADING_HOLD6") (pin "1") (pinfunction "1_1") (pintype "unspecified+no_connect"))
    )
    (net (code "84") (name "unconnected-(HEADING_HOLD6-Pad4)") (class "Default")
      (node (ref "HEADING_HOLD6") (pin "4") (pinfunction "4_4") (pintype "unspecified+no_connect"))
    )
    (net (code "85") (name "unconnected-(HEADING_HOLD7-Pad1)") (class "Default")
      (node (ref "HEADING_HOLD7") (pin "1") (pinfunction "1_1") (pintype "unspecified+no_connect"))
    )
    (net (code "86") (name "unconnected-(HEADING_HOLD7-Pad4)") (class "Default")
      (node (ref "HEADING_HOLD7") (pin "4") (pinfunction "4_4") (pintype "unspecified+no_connect"))
    )
    (net (code "87") (name "unconnected-(HEADING_HOLD8-Pad1)") (class "Default")
      (node (ref "HEADING_HOLD8") (pin "1") (pinfunction "1_1") (pintype "unspecified+no_connect"))
    )
    (net (code "88") (name "unconnected-(HEADING_HOLD8-Pad4)") (class "Default")
      (node (ref "HEADING_HOLD8") (pin "4") (pinfunction "4_4") (pintype "unspecified+no_connect"))
    )
    (net (code "89") (name "unconnected-(HEADING_HOLD9-Pad1)") (class "Default")
      (node (ref "HEADING_HOLD9") (pin "1") (pinfunction "1_1") (pintype "unspecified+no_connect"))
    )
    (net (code "90") (name "unconnected-(HEADING_HOLD9-Pad4)") (class "Default")
      (node (ref "HEADING_HOLD9") (pin "4") (pinfunction "4_4") (pintype "unspecified+no_connect"))
    )
    (net (code "91") (name "unconnected-(HEADING_HOLD10-Pad1)") (class "Default")
      (node (ref "HEADING_HOLD10") (pin "1") (pinfunction "1_1") (pintype "unspecified+no_connect"))
    )
    (net (code "92") (name "unconnected-(HEADING_HOLD10-Pad4)") (class "Default")
      (node (ref "HEADING_HOLD10") (pin "4") (pinfunction "4_4") (pintype "unspecified+no_connect"))
    )
    (net (code "93") (name "unconnected-(PANEL_DIMMER-EH-Pad4)") (class "Default")
      (node (ref "PANEL_DIMMER") (pin "4") (pinfunction "EH_4") (pintype "unspecified+no_connect"))
    )
    (net (code "94") (name "unconnected-(PANEL_DIMMER-EH-Pad5)") (class "Default")
      (node (ref "PANEL_DIMMER") (pin "5") (pinfunction "EH_5") (pintype "unspecified+no_connect"))
    )
    (net (code "95") (name "unconnected-(PFD1_MFD1-Pad6)") (class "Default")
      (node (ref "PFD1_MFD1") (pin "6") (pinfunction "6_6") (pintype "unspecified+no_connect"))
    )
    (net (code "96") (name "unconnected-(PFD1_MFD1-Pad7)") (class "Default")
      (node (ref "PFD1_MFD1") (pin "7") (pinfunction "7_7") (pintype "unspecified+no_connect"))
    )
    (net (code "97") (name "unconnected-(PFD2_MFD2-Pad6)") (class "Default")
      (node (ref "PFD2_MFD2") (pin "6") (pinfunction "6_6") (pintype "unspecified+no_connect"))
    )
    (net (code "98") (name "unconnected-(PFD2_MFD2-Pad7)") (class "Default")
      (node (ref "PFD2_MFD2") (pin "7") (pinfunction "7_7") (pintype "unspecified+no_connect"))
    )
    (net (code "99") (name "unconnected-(U2-3.3V-Pad79)") (class "Default")
      (node (ref "U2") (pin "79") (pinfunction "3.3V_79") (pintype "unspecified+no_connect"))
    )
    (net (code "100") (name "unconnected-(U2-3.3V-Pad80)") (class "Default")
      (node (ref "U2") (pin "80") (pinfunction "3.3V_80") (pintype "unspecified+no_connect"))
    )
    (net (code "101") (name "unconnected-(U2-5V-Pad39)") (class "Default")
      (node (ref "U2") (pin "39") (pinfunction "5V_39") (pintype "unspecified+no_connect"))
    )
    (net (code "102") (name "unconnected-(U2-5V-Pad82)") (class "Default")
      (node (ref "U2") (pin "82") (pinfunction "5V_82") (pintype "unspecified+no_connect"))
    )
    (net (code "103") (name "unconnected-(U2-A11-Pad12)") (class "Default")
      (node (ref "U2") (pin "12") (pinfunction "A11_12") (pintype "unspecified+no_connect"))
    )
    (net (code "104") (name "unconnected-(U2-A12-Pad13)") (class "Default")
      (node (ref "U2") (pin "13") (pinfunction "A12_13") (pintype "unspecified+no_connect"))
    )
    (net (code "105") (name "unconnected-(U2-A13-Pad14)") (class "Default")
      (node (ref "U2") (pin "14") (pinfunction "A13_14") (pintype "unspecified+no_connect"))
    )
    (net (code "106") (name "unconnected-(U2-A14-Pad15)") (class "Default")
      (node (ref "U2") (pin "15") (pinfunction "A14_15") (pintype "unspecified+no_connect"))
    )
    (net (code "107") (name "unconnected-(U2-A15-Pad16)") (class "Default")
      (node (ref "U2") (pin "16") (pinfunction "A15_16") (pintype "unspecified+no_connect"))
    )
    (net (code "108") (name "unconnected-(U2-AREF-Pad78)") (class "Default")
      (node (ref "U2") (pin "78") (pinfunction "AREF_78") (pintype "unspecified+no_connect"))
    )
    (net (code "109") (name "unconnected-(U2-D24-Pad52)") (class "Default")
      (node (ref "U2") (pin "52") (pinfunction "D24_52") (pintype "unspecified+no_connect"))
    )
    (net (code "110") (name "unconnected-(U2-D25-Pad51)") (class "Default")
      (node (ref "U2") (pin "51") (pinfunction "D25_51") (pintype "unspecified+no_connect"))
    )
    (net (code "111") (name "unconnected-(U2-D26-Pad50)") (class "Default")
      (node (ref "U2") (pin "50") (pinfunction "D26_50") (pintype "unspecified+no_connect"))
    )
    (net (code "112") (name "unconnected-(U2-D27-Pad49)") (class "Default")
      (node (ref "U2") (pin "49") (pinfunction "D27_49") (pintype "unspecified+no_connect"))
    )
    (net (code "113") (name "unconnected-(U2-D28-Pad48)") (class "Default")
      (node (ref "U2") (pin "48") (pinfunction "D28_48") (pintype "unspecified+no_connect"))
    )
    (net (code "114") (name "unconnected-(U2-D29-Pad47)") (class "Default")
      (node (ref "U2") (pin "47") (pinfunction "D29_47") (pintype "unspecified+no_connect"))
    )
    (net (code "115") (name "unconnected-(U2-D30-Pad46)") (class "Default")
      (node (ref "U2") (pin "46") (pinfunction "D30_46") (pintype "unspecified+no_connect"))
    )
    (net (code "116") (name "unconnected-(U2-D31-Pad45)") (class "Default")
      (node (ref "U2") (pin "45") (pinfunction "D31_45") (pintype "unspecified+no_connect"))
    )
    (net (code "117") (name "unconnected-(U2-D32-Pad17)") (class "Default")
      (node (ref "U2") (pin "17") (pinfunction "D32_17") (pintype "unspecified+no_connect"))
    )
    (net (code "118") (name "unconnected-(U2-D33-Pad18)") (class "Default")
      (node (ref "U2") (pin "18") (pinfunction "D33_18") (pintype "unspecified+no_connect"))
    )
    (net (code "119") (name "unconnected-(U2-D34-Pad19)") (class "Default")
      (node (ref "U2") (pin "19") (pinfunction "D34_19") (pintype "unspecified+no_connect"))
    )
    (net (code "120") (name "unconnected-(U2-D35-Pad20)") (class "Default")
      (node (ref "U2") (pin "20") (pinfunction "D35_20") (pintype "unspecified+no_connect"))
    )
    (net (code "121") (name "unconnected-(U2-D36-Pad21)") (class "Default")
      (node (ref "U2") (pin "21") (pinfunction "D36_21") (pintype "unspecified+no_connect"))
    )
    (net (code "122") (name "unconnected-(U2-D37-Pad22)") (class "Default")
      (node (ref "U2") (pin "22") (pinfunction "D37_22") (pintype "unspecified+no_connect"))
    )
    (net (code "123") (name "unconnected-(U2-D38-Pad23)") (class "Default")
      (node (ref "U2") (pin "23") (pinfunction "D38_23") (pintype "unspecified+no_connect"))
    )
    (net (code "124") (name "unconnected-(U2-D39-Pad24)") (class "Default")
      (node (ref "U2") (pin "24") (pinfunction "D39_24") (pintype "unspecified+no_connect"))
    )
    (net (code "125") (name "unconnected-(U2-D40-Pad25)") (class "Default")
      (node (ref "U2") (pin "25") (pinfunction "D40_25") (pintype "unspecified+no_connect"))
    )
    (net (code "126") (name "unconnected-(U2-D41-Pad26)") (class "Default")
      (node (ref "U2") (pin "26") (pinfunction "D41_26") (pintype "unspecified+no_connect"))
    )
    (net (code "127") (name "unconnected-(U2-D42-Pad27)") (class "Default")
      (node (ref "U2") (pin "27") (pinfunction "D42_27") (pintype "unspecified+no_connect"))
    )
    (net (code "128") (name "unconnected-(U2-D43-Pad28)") (class "Default")
      (node (ref "U2") (pin "28") (pinfunction "D43_28") (pintype "unspecified+no_connect"))
    )
    (net (code "129") (name "unconnected-(U2-D44-Pad29)") (class "Default")
      (node (ref "U2") (pin "29") (pinfunction "D44_29") (pintype "unspecified+no_connect"))
    )
    (net (code "130") (name "unconnected-(U2-D45-Pad30)") (class "Default")
      (node (ref "U2") (pin "30") (pinfunction "D45_30") (pintype "unspecified+no_connect"))
    )
    (net (code "131") (name "unconnected-(U2-D46-Pad31)") (class "Default")
      (node (ref "U2") (pin "31") (pinfunction "D46_31") (pintype "unspecified+no_connect"))
    )
    (net (code "132") (name "unconnected-(U2-D47-Pad32)") (class "Default")
      (node (ref "U2") (pin "32") (pinfunction "D47_32") (pintype "unspecified+no_connect"))
    )
    (net (code "133") (name "unconnected-(U2-D48-Pad33)") (class "Default")
      (node (ref "U2") (pin "33") (pinfunction "D48_33") (pintype "unspecified+no_connect"))
    )
    (net (code "134") (name "unconnected-(U2-D49-Pad34)") (class "Default")
      (node (ref "U2") (pin "34") (pinfunction "D49_34") (pintype "unspecified+no_connect"))
    )
    (net (code "135") (name "unconnected-(U2-D50-Pad35)") (class "Default")
      (node (ref "U2") (pin "35") (pinfunction "D50_35") (pintype "unspecified+no_connect"))
    )
    (net (code "136") (name "unconnected-(U2-D51-Pad36)") (class "Default")
      (node (ref "U2") (pin "36") (pinfunction "D51_36") (pintype "unspecified+no_connect"))
    )
    (net (code "137") (name "unconnected-(U2-D52-Pad37)") (class "Default")
      (node (ref "U2") (pin "37") (pinfunction "D52_37") (pintype "unspecified+no_connect"))
    )
    (net (code "138") (name "unconnected-(U2-D53-Pad38)") (class "Default")
      (node (ref "U2") (pin "38") (pinfunction "D53_38") (pintype "unspecified+no_connect"))
    )
    (net (code "139") (name "unconnected-(U2-MISO-Pad40)") (class "Default")
      (node (ref "U2") (pin "40") (pinfunction "MISO_40") (pintype "unspecified+no_connect"))
    )
    (net (code "140") (name "unconnected-(U2-MOSI-Pad41)") (class "Default")
      (node (ref "U2") (pin "41") (pinfunction "MOSI_41") (pintype "unspecified+no_connect"))
    )
    (net (code "141") (name "unconnected-(U2-RX-Pad76)") (class "Default")
      (node (ref "U2") (pin "76") (pinfunction "RX_76") (pintype "unspecified+no_connect"))
    )
    (net (code "142") (name "unconnected-(U2-Reset-Pad44)") (class "Default")
      (node (ref "U2") (pin "44") (pinfunction "Reset_44") (pintype "unspecified+no_connect"))
    )
    (net (code "143") (name "unconnected-(U2-Reset-Pad77)") (class "Default")
      (node (ref "U2") (pin "77") (pinfunction "Reset_77") (pintype "unspecified+no_connect"))
    )
    (net (code "144") (name "unconnected-(U2-TX-Pad75)") (class "Default")
      (node (ref "U2") (pin "75") (pinfunction "TX_75") (pintype "unspecified+no_connect"))
    )
    (net (code "145") (name "unconnected-(U2-VIN-Pad85)") (class "Default")
      (node (ref "U2") (pin "85") (pinfunction "VIN_85") (pintype "unspecified+no_connect"))
    )
    (net (code "146") (name "unconnected-(U2-VIN-Pad86)") (class "Default")
      (node (ref "U2") (pin "86") (pinfunction "VIN_86") (pintype "unspecified+no_connect"))
    )
  )
)
